# Infrared.net
KiCad netlist of a schematic drawn in Altium Designer
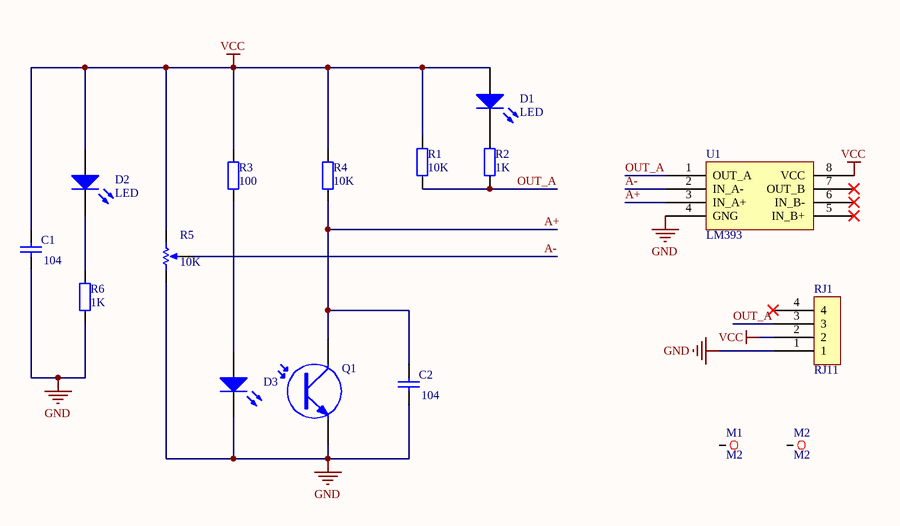
[diagram p0: Infrared.SchDoc]

(export (version "E")
  (design (tool "Eeschema 10.0.6"))
  (components
    (comp (ref "C1")
      (value "104")
      (footprint "0603_C")
      (description "Capacitor")
      (fields (field (name "Comment") "Cap") (field (name "PUBLISHER") "Altium Limited"))
      (libsource (lib "Miscellaneous Devices") (part "Cap"))
    )
    (comp (ref "C2")
      (value "104")
      (footprint "0603_C")
      (description "Capacitor")
      (fields (field (name "Comment") "Cap") (field (name "PUBLISHER") "Altium Limited"))
      (libsource (lib "Miscellaneous Devices") (part "Cap"))
    )
    (comp (ref "D1")
      (value "LED")
      (footprint "0805")
      (description "Typical RED GaAs LED")
      (fields (field (name "PUBLISHER") "Altium Limited"))
      (libsource (lib "Miscellaneous Devices") (part "LED1"))
    )
    (comp (ref "D2")
      (value "LED")
      (footprint "0805")
      (description "Typical RED GaAs LED")
      (fields (field (name "PUBLISHER") "Altium Limited"))
      (libsource (lib "Miscellaneous Devices") (part "LED1"))
    )
    (comp (ref "D3")
      (value "Infrared")
      (footprint "红外")
      (description "Typical RED GaAs LED")
      (fields (field (name "PUBLISHER") "Altium Limited"))
      (libsource (lib "Miscellaneous Devices") (part "LED1"))
    )
    (comp (ref "M1") (value "M2") (footprint "M2") (libsource (lib "QQW-1.SCHLIB") (part "M3")))
    (comp (ref "M2") (value "M2") (footprint "M2") (libsource (lib "QQW-1.SCHLIB") (part "M3")))
    (comp (ref "Q1")
      (value "Photo NPN")
      (footprint "红外")
      (description "NPN Phototransistor")
      (fields (field (name "PUBLISHER") "Altium Limited"))
      (libsource (lib "Miscellaneous Devices") (part "Photo NPN"))
    )
    (comp (ref "R1")
      (value "10K")
      (footprint "0603_R")
      (description "Resistor")
      (fields (field (name "Comment") "Res2") (field (name "PUBLISHER") "Altium Limited"))
      (libsource (lib "Miscellaneous Devices") (part "Res2"))
    )
    (comp (ref "R2")
      (value "1K")
      (footprint "0603_R")
      (description "Resistor")
      (fields (field (name "Comment") "Res2") (field (name "PUBLISHER") "Altium Limited"))
      (libsource (lib "Miscellaneous Devices") (part "Res2"))
    )
    (comp (ref "R3")
      (value "100")
      (footprint "0603_R")
      (description "Resistor")
      (fields (field (name "Comment") "Res2") (field (name "PUBLISHER") "Altium Limited"))
      (libsource (lib "Miscellaneous Devices") (part "Res2"))
    )
    (comp (ref "R4")
      (value "10K")
      (footprint "0603_R")
      (description "Resistor")
      (fields (field (name "Comment") "Res2") (field (name "PUBLISHER") "Altium Limited"))
      (libsource (lib "Miscellaneous Devices") (part "Res2"))
    )
    (comp (ref "R5")
      (value "10K")
      (footprint "电位器")
      (description "Potentiometer")
      (fields (field (name "Comment") "RPot") (field (name "PUBLISHER") "Altium Limited"))
      (libsource (lib "Miscellaneous Devices") (part "RPot"))
    )
    (comp (ref "R6")
      (value "1K")
      (footprint "0603_R")
      (description "Resistor")
      (fields (field (name "Comment") "Res2") (field (name "PUBLISHER") "Altium Limited"))
      (libsource (lib "Miscellaneous Devices") (part "Res2"))
    )
    (comp (ref "RJ1") (value "RJ11") (footprint "RJ11") (libsource (lib "少儿智能车") (part "RJ11")))
    (comp (ref "U1") (value "LM393") (footprint "SO-8") (libsource (lib "Infrared") (part "LM393")))
  )
  (nets
    (net (code "1") (name "/A+") (class "Default")
      (node (ref "C2") (pin "2") (pinfunction "2_2") (pintype "passive"))
      (node (ref "Q1") (pin "2") (pinfunction "C_2") (pintype "passive"))
      (node (ref "R4") (pin "1") (pinfunction "1_1") (pintype "passive"))
      (node (ref "U1") (pin "3") (pinfunction "IN_A+_3") (pintype "passive"))
    )
    (net (code "2") (name "/A-") (class "Default")
      (node (ref "R5") (pin "3") (pinfunction "TAP_3") (pintype "passive"))
      (node (ref "U1") (pin "2") (pinfunction "IN_A-_2") (pintype "passive"))
    )
    (net (code "3") (name "/OUT_A") (class "Default")
      (node (ref "R1") (pin "1") (pinfunction "1_1") (pintype "passive"))
      (node (ref "R2") (pin "1") (pinfunction "1_1") (pintype "passive"))
      (node (ref "RJ1") (pin "3") (pinfunction "3_3") (pintype "passive"))
      (node (ref "U1") (pin "1") (pinfunction "OUT_A_1") (pintype "passive"))
    )
    (net (code "4") (name "GND") (class "Default")
      (node (ref "C1") (pin "1") (pinfunction "1_1") (pintype "passive"))
      (node (ref "C2") (pin "1") (pinfunction "1_1") (pintype "passive"))
      (node (ref "D3") (pin "2") (pinfunction "K_2") (pintype "passive"))
      (node (ref "Q1") (pin "1") (pinfunction "E_1") (pintype "passive"))
      (node (ref "R5") (pin "1") (pinfunction "TOP_1") (pintype "passive"))
      (node (ref "R6") (pin "1") (pinfunction "1_1") (pintype "passive"))
      (node (ref "RJ1") (pin "1") (pinfunction "1_1") (pintype "passive"))
      (node (ref "U1") (pin "4") (pinfunction "GNG_4") (pintype "passive"))
    )
    (net (code "5") (name "Net-(D1-K)") (class "Default")
      (node (ref "D1") (pin "2") (pinfunction "K_2") (pintype "passive"))
      (node (ref "R2") (pin "2") (pinfunction "2_2") (pintype "passive"))
    )
    (net (code "6") (name "Net-(D2-K)") (class "Default")
      (node (ref "D2") (pin "2") (pinfunction "K_2") (pintype "passive"))
      (node (ref "R6") (pin "2") (pinfunction "2_2") (pintype "passive"))
    )
    (net (code "7") (name "Net-(D3-A)") (class "Default")
      (node (ref "D3") (pin "1") (pinfunction "A_1") (pintype "passive"))
      (node (ref "R3") (pin "1") (pinfunction "1_1") (pintype "passive"))
    )
    (net (code "8") (name "VCC") (class "Default")
      (node (ref "C1") (pin "2") (pinfunction "2_2") (pintype "passive"))
      (node (ref "D1") (pin "1") (pinfunction "A_1") (pintype "passive"))
      (node (ref "D2") (pin "1") (pinfunction "A_1") (pintype "passive"))
      (node (ref "R1") (pin "2") (pinfunction "2_2") (pintype "passive"))
      (node (ref "R3") (pin "2") (pinfunction "2_2") (pintype "passive"))
      (node (ref "R4") (pin "2") (pinfunction "2_2") (pintype "passive"))
      (node (ref "R5") (pin "2") (pinfunction "BOT_2") (pintype "passive"))
      (node (ref "RJ1") (pin "2") (pinfunction "2_2") (pintype "passive"))
      (node (ref "U1") (pin "8") (pinfunction "VCC_8") (pintype "passive"))
    )
    (net (code "9") (name "unconnected-(M1-Pad0)") (class "Default")
      (node (ref "M1") (pin "0") (pinfunction "0_0") (pintype "passive"))
    )
    (net (code "10") (name "unconnected-(M2-Pad0)") (class "Default")
      (node (ref "M2") (pin "0") (pinfunction "0_0") (pintype "passive"))
    )
    (net (code "11") (name "unconnected-(RJ1-Pad4)") (class "Default")
      (node (ref "RJ1") (pin "4") (pinfunction "4_4") (pintype "passive+no_connect"))
    )
    (net (code "12") (name "unconnected-(U1-IN_B+-Pad5)") (class "Default")
      (node (ref "U1") (pin "5") (pinfunction "IN_B+_5") (pintype "passive+no_connect"))
    )
    (net (code "13") (name "unconnected-(U1-IN_B--Pad6)") (class "Default")
      (node (ref "U1") (pin "6") (pinfunction "IN_B-_6") (pintype "passive+no_connect"))
    )
    (net (code "14") (name "unconnected-(U1-OUT_B-Pad7)") (class "Default")
      (node (ref "U1") (pin "7") (pinfunction "OUT_B_7") (pintype "passive+no_connect"))
    )
  )
)
